# BSPD_Simulation.net
KiCad netlist of a schematic drawn in Altium Designer
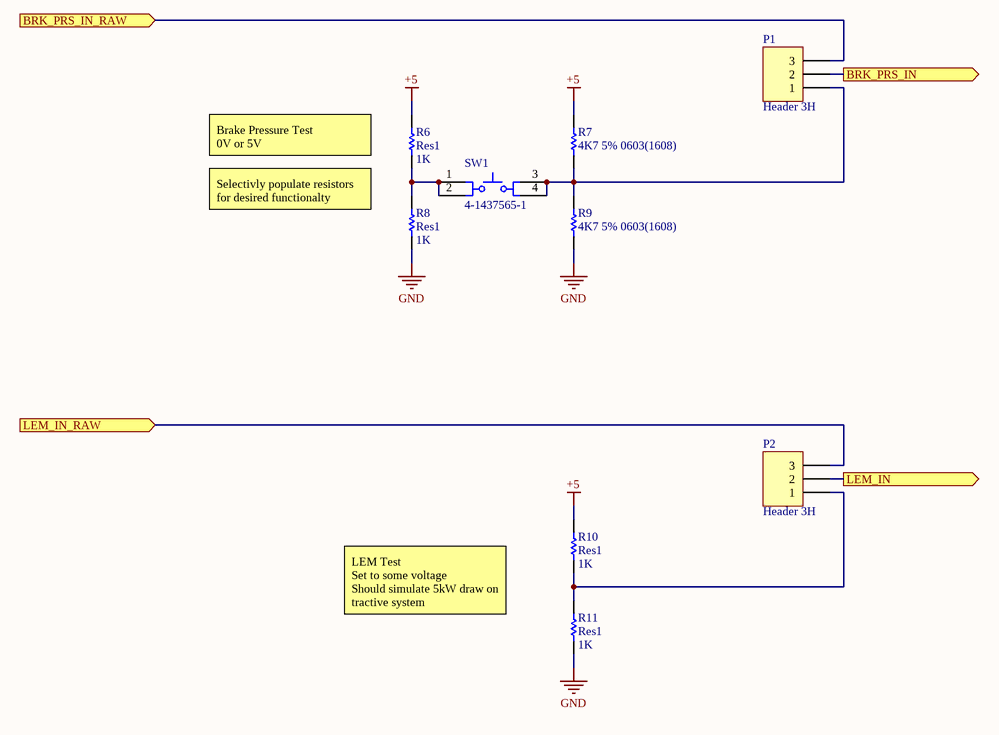
[diagram p0: BSPD_Simulation.SchDoc]

(export (version "E")
  (design (tool "Eeschema 10.0.6"))
  (components
    (comp (ref "P1")
      (value "Header 3H")
      (footprint "HDR1X3H")
      (description "Header, 3-Pin, Right Angle")
      (fields (field (name "PUBLISHER") "Altium Limited"))
      (libsource (lib "Miscellaneous Connectors") (part "Header 3H"))
    )
    (comp (ref "P2")
      (value "Header 3H")
      (footprint "HDR1X3H")
      (description "Header, 3-Pin, Right Angle")
      (fields (field (name "PUBLISHER") "Altium Limited"))
      (libsource (lib "Miscellaneous Connectors") (part "Header 3H"))
    )
    (comp (ref "R6")
      (value "Res1")
      (footprint "AXIAL-0.3")
      (description "Resistor")
      (fields (field (name "ALTIUM_VALUE") "1K") (field (name "PUBLISHER") "Altium Limited"))
      (libsource (lib "Miscellaneous Devices") (part "Res1"))
    )
    (comp (ref "R7")
      (value "4K7 5% 0603(1608)")
      (footprint "RESC0603(1608)_N")
      (description "4K7 0.1W 5% 0603 (1608 Metric)  SMD")
      (fields (field (name "TOLERANCE") "5 %") (field (name "POWER") "0.1 W"))
      (libsource (lib "Altium Content Vault") (part "RES"))
    )
    (comp (ref "R8")
      (value "Res1")
      (footprint "AXIAL-0.3")
      (description "Resistor")
      (fields (field (name "ALTIUM_VALUE") "1K") (field (name "PUBLISHER") "Altium Limited"))
      (libsource (lib "Miscellaneous Devices") (part "Res1"))
    )
    (comp (ref "R9")
      (value "4K7 5% 0603(1608)")
      (footprint "RESC0603(1608)_N")
      (description "4K7 0.1W 5% 0603 (1608 Metric)  SMD")
      (fields (field (name "TOLERANCE") "5 %") (field (name "POWER") "0.1 W"))
      (libsource (lib "Altium Content Vault") (part "RES"))
    )
    (comp (ref "R10")
      (value "Res1")
      (footprint "AXIAL-0.3")
      (description "Resistor")
      (fields (field (name "ALTIUM_VALUE") "1K") (field (name "PUBLISHER") "Altium Limited"))
      (libsource (lib "Miscellaneous Devices") (part "Res1"))
    )
    (comp (ref "R11")
      (value "Res1")
      (footprint "AXIAL-0.3")
      (description "Resistor")
      (fields (field (name "ALTIUM_VALUE") "1K") (field (name "PUBLISHER") "Altium Limited"))
      (libsource (lib "Miscellaneous Devices") (part "Res1"))
    )
    (comp (ref "SW1")
      (value "4-1437565-1")
      (footprint "TECO-4-1437565-1_V")
      (description "Tactile Switch, 50 mA, 12 VDC, -20 to 85 degC, 4-Pin SMD, RoHS, Bulk")
      (fields (field (name "MANUFACTURER") "TEConnectivity/AMPBrand"))
      (libsource (lib "Altium Content Vault") (part "SW-SPST-NO-4"))
    )
  )
  (nets
    (net (code "1") (name "+5") (class "Default")
      (node (ref "R10") (pin "2") (pinfunction "2_2") (pintype "passive"))
      (node (ref "R6") (pin "2") (pinfunction "2_2") (pintype "passive"))
      (node (ref "R7") (pin "2") (pinfunction "2_2") (pintype "passive"))
    )
    (net (code "2") (name "/BRK_PRS_IN") (class "Default")
      (node (ref "P1") (pin "2") (pinfunction "2_2") (pintype "passive"))
    )
    (net (code "3") (name "/BRK_PRS_IN_RAW") (class "Default")
      (node (ref "P1") (pin "3") (pinfunction "3_3") (pintype "passive"))
    )
    (net (code "4") (name "/LEM_IN") (class "Default")
      (node (ref "P2") (pin "2") (pinfunction "2_2") (pintype "passive"))
    )
    (net (code "5") (name "/LEM_IN_RAW") (class "Default")
      (node (ref "P2") (pin "3") (pinfunction "3_3") (pintype "passive"))
    )
    (net (code "6") (name "GND") (class "Default")
      (node (ref "R11") (pin "1") (pinfunction "1_1") (pintype "passive"))
      (node (ref "R8") (pin "1") (pinfunction "1_1") (pintype "passive"))
      (node (ref "R9") (pin "1") (pinfunction "1_1") (pintype "passive"))
    )
    (net (code "7") (name "Net-(P1-Pad1)") (class "Default")
      (node (ref "P1") (pin "1") (pinfunction "1_1") (pintype "passive"))
      (node (ref "R7") (pin "1") (pinfunction "1_1") (pintype "passive"))
      (node (ref "R9") (pin "2") (pinfunction "2_2") (pintype "passive"))
      (node (ref "SW1") (pin "3") (pinfunction "3_3") (pintype "passive"))
      (node (ref "SW1") (pin "4") (pinfunction "4_4") (pintype "passive"))
    )
    (net (code "8") (name "Net-(P2-Pad1)") (class "Default")
      (node (ref "P2") (pin "1") (pinfunction "1_1") (pintype "passive"))
      (node (ref "R10") (pin "1") (pinfunction "1_1") (pintype "passive"))
      (node (ref "R11") (pin "2") (pinfunction "2_2") (pintype "passive"))
    )
    (net (code "9") (name "Net-(R6-Pad1)") (class "Default")
      (node (ref "R6") (pin "1") (pinfunction "1_1") (pintype "passive"))
      (node (ref "R8") (pin "2") (pinfunction "2_2") (pintype "passive"))
      (node (ref "SW1") (pin "1") (pinfunction "1_1") (pintype "passive"))
      (node (ref "SW1") (pin "2") (pinfunction "2_2") (pintype "passive"))
    )
  )
)
